# PP7_USB.net
KiCad netlist of a schematic drawn in Altium Designer
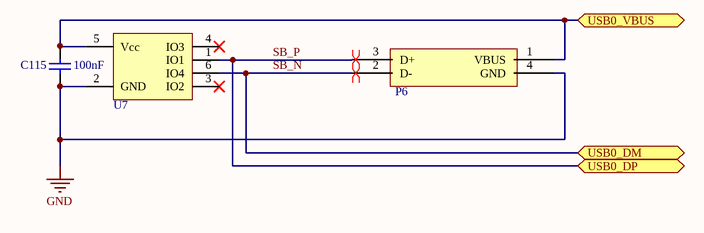
[diagram p0: PP7_USB.SchDoc]

(export (version "E")
  (design (tool "Eeschema 10.0.6"))
  (components
    (comp (ref "C115")
      (value "100nF")
      (footprint "CAPC1608X08")
      (description "Capacitor")
      (fields (field (name "Comment") "Cap 100nF"))
      (libsource (lib "Michel") (part "Cap Semi"))
    )
    (comp (ref "P6")
      (value "1734346-1")
      (footprint "CONN4-292304")
      (description "Connecteur USB-Type-B")
      (libsource (lib "Michel") (part "67068-8010"))
    )
    (comp (ref "U7")
      (value "TPD4E1U06DBVR")
      (footprint "DBV6-M")
      (description "Protection_ESD")
      (libsource (lib "Michel") (part "TPD4E1U06DBVR"))
    )
  )
  (nets
    (net (code "1") (name "/SB_N") (class "Default")
      (node (ref "P6") (pin "2") (pinfunction "D-_2") (pintype "passive"))
      (node (ref "U7") (pin "6") (pinfunction "IO4_6") (pintype "passive"))
    )
    (net (code "2") (name "/SB_P") (class "Default")
      (node (ref "P6") (pin "3") (pinfunction "D+_3") (pintype "passive"))
      (node (ref "U7") (pin "1") (pinfunction "IO1_1") (pintype "passive"))
    )
    (net (code "3") (name "/USB0_VBUS") (class "Default")
      (node (ref "C115") (pin "1") (pinfunction "1_1") (pintype "passive"))
      (node (ref "P6") (pin "1") (pinfunction "VBUS_1") (pintype "passive"))
      (node (ref "U7") (pin "5") (pinfunction "Vcc_5") (pintype "passive"))
    )
    (net (code "4") (name "GND") (class "Default")
      (node (ref "C115") (pin "2") (pinfunction "2_2") (pintype "passive"))
      (node (ref "P6") (pin "4") (pinfunction "GND_4") (pintype "passive"))
      (node (ref "U7") (pin "2") (pinfunction "GND_2") (pintype "passive"))
    )
    (net (code "5") (name "unconnected-(U7-IO2-Pad3)") (class "Default")
      (node (ref "U7") (pin "3") (pinfunction "IO2_3") (pintype "passive+no_connect"))
    )
    (net (code "6") (name "unconnected-(U7-IO3-Pad4)") (class "Default")
      (node (ref "U7") (pin "4") (pinfunction "IO3_4") (pintype "passive+no_connect"))
    )
  )
)
